# badge.net
KiCad netlist of a schematic drawn in Altium Designer
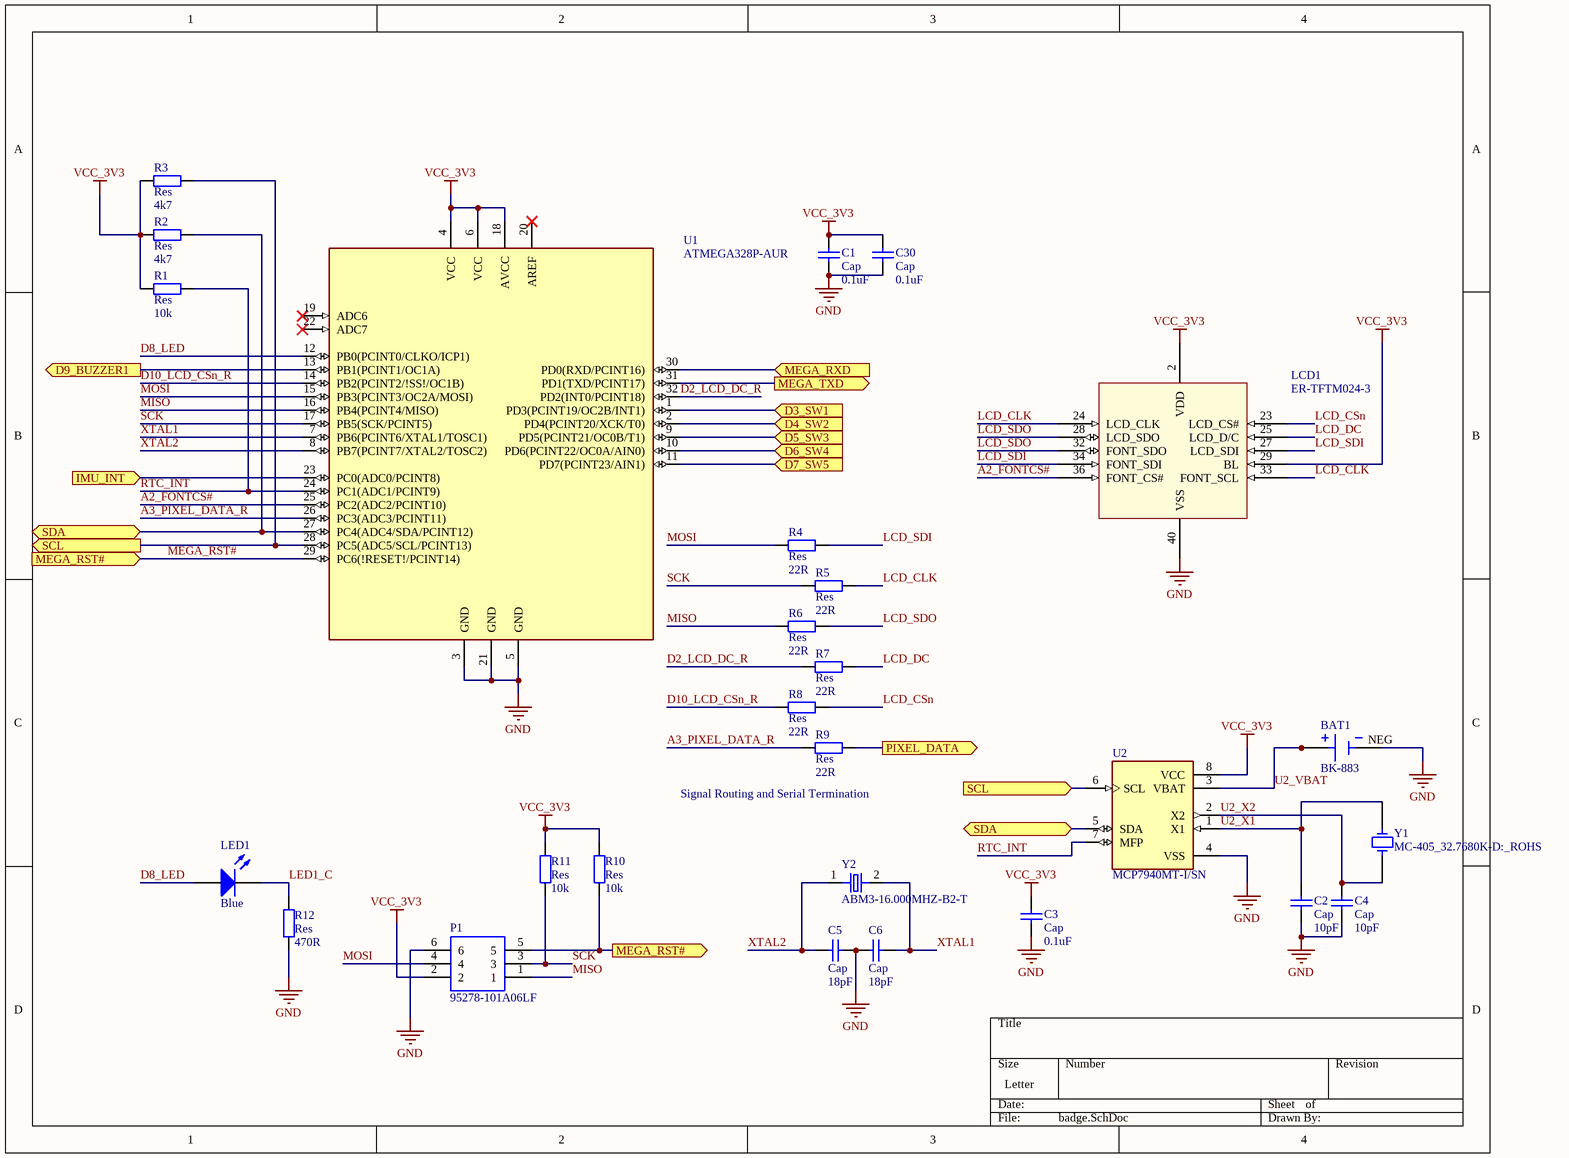
[diagram p0: badge.SchDoc]

(export (version "E")
  (design (tool "Eeschema 10.0.6"))
  (components
    (comp (ref "BAT1")
      (value "BK-883")
      (footprint "BAT_BK-883")
      (description "Battery Retainer Coin, 20.0mm 1 Cell SMD _SMT_ Tab")
      (fields (field (name "MF") "MPD _Memory") (field (name "MP") "BK-883-TR"))
      (libsource (lib "badge") (part "BK-883"))
    )
    (comp (ref "C1")
      (value "Cap")
      (footprint "C0603")
      (description "Capacitor")
      (fields
        (field (name "ALTIUM_VALUE") "0.1uF")
        (field (name "MP") "C0603C104Z3VACTU")
        (field (name "MF") "KEMET")
        (field (name "PUBLISHER") "Altium Limited")
      )
      (libsource (lib "badge") (part "Cap"))
    )
    (comp (ref "C2")
      (value "Cap")
      (footprint "C0603")
      (description "Capacitor")
      (fields
        (field (name "ALTIUM_VALUE") "10pF")
        (field (name "MF") "KEMET")
        (field (name "MP") "C0603C100J1GACTU")
        (field (name "PUBLISHER") "Altium Limited")
      )
      (libsource (lib "badge") (part "Cap"))
    )
    (comp (ref "C3")
      (value "Cap")
      (footprint "C0603")
      (description "Capacitor")
      (fields
        (field (name "ALTIUM_VALUE") "0.1uF")
        (field (name "MF") "KEMET")
        (field (name "MP") "C0603C104M4RACTU")
        (field (name "PUBLISHER") "Altium Limited")
      )
      (libsource (lib "badge") (part "Cap"))
    )
    (comp (ref "C4")
      (value "Cap")
      (footprint "C0603")
      (description "Capacitor")
      (fields
        (field (name "ALTIUM_VALUE") "10pF")
        (field (name "MF") "KEMET")
        (field (name "MP") "C0603C100J1GACTU")
        (field (name "PUBLISHER") "Altium Limited")
      )
      (libsource (lib "badge") (part "Cap"))
    )
    (comp (ref "C5")
      (value "Cap")
      (footprint "C0603")
      (description "Capacitor")
      (fields
        (field (name "ALTIUM_VALUE") "18pF")
        (field (name "MF") "KEMET")
        (field (name "MP") "C0603C180J5GACTU")
        (field (name "PUBLISHER") "Altium Limited")
      )
      (libsource (lib "badge") (part "Cap"))
    )
    (comp (ref "C6")
      (value "Cap")
      (footprint "C0603")
      (description "Capacitor")
      (fields
        (field (name "ALTIUM_VALUE") "18pF")
        (field (name "MF") "KEMET")
        (field (name "MP") "C0603C180J5GACTU")
        (field (name "PUBLISHER") "Altium Limited")
      )
      (libsource (lib "badge") (part "Cap"))
    )
    (comp (ref "C30")
      (value "Cap")
      (footprint "C0603")
      (description "Capacitor")
      (fields
        (field (name "ALTIUM_VALUE") "0.1uF")
        (field (name "MF") "KEMET")
        (field (name "MP") "C0603C104Z3VACTU")
        (field (name "PUBLISHER") "Altium Limited")
      )
      (libsource (lib "badge") (part "Cap"))
    )
    (comp (ref "LCD1")
      (value "ER-TFTM024-3")
      (footprint "ER-TFTM024-3")
      (fields (field (name "MF") "DNP"))
      (libsource (lib "badge") (part "ER-TFTM024-3"))
    )
    (comp (ref "LED1")
      (value "Blue")
      (footprint "L0603")
      (description "Typical INFRARED GaAs LED")
      (fields
        (field (name "MF") "OSRAM")
        (field (name "MP") "LB Q39G-L2OO-35-1")
        (field (name "PUBLISHER") "Altium Limited")
      )
      (libsource (lib "badge") (part "LED"))
    )
    (comp (ref "P1")
      (value "95278-101A06LF")
      (footprint "AMPHENOL_95278-101A06LF")
      (description "Connector Header Surface Mount 6 position 0.100 _2.54mm_")
      (fields (field (name "MF") "Amphenol ICC"))
      (libsource (lib "badge") (part "95278-101A06LF"))
    )
    (comp (ref "R1")
      (value "Res")
      (footprint "R0603")
      (description "Resistor")
      (fields
        (field (name "ALTIUM_VALUE") "10k")
        (field (name "MP") "RC0603JR-0710KL")
        (field (name "MF") "Yageo")
        (field (name "PUBLISHER") "Altium Limited")
      )
      (libsource (lib "badge") (part "Res"))
    )
    (comp (ref "R2")
      (value "Res")
      (footprint "R0603")
      (description "Resistor")
      (fields
        (field (name "ALTIUM_VALUE") "4k7")
        (field (name "MF") "Yageo")
        (field (name "MP") "RC0603JR-074K7L")
        (field (name "PUBLISHER") "Altium Limited")
      )
      (libsource (lib "badge") (part "Res"))
    )
    (comp (ref "R3")
      (value "Res")
      (footprint "R0603")
      (description "Resistor")
      (fields
        (field (name "ALTIUM_VALUE") "4k7")
        (field (name "MF") "Yageo")
        (field (name "MP") "RC0603JR-074K7L")
        (field (name "PUBLISHER") "Altium Limited")
      )
      (libsource (lib "badge") (part "Res"))
    )
    (comp (ref "R4")
      (value "Res")
      (footprint "R0603")
      (description "Resistor")
      (fields
        (field (name "ALTIUM_VALUE") "22R")
        (field (name "MF") "TE Connectivity")
        (field (name "MP") "CRGCQ0603J22R")
        (field (name "PUBLISHER") "Altium Limited")
      )
      (libsource (lib "badge") (part "Res"))
    )
    (comp (ref "R5")
      (value "Res")
      (footprint "R0603")
      (description "Resistor")
      (fields
        (field (name "ALTIUM_VALUE") "22R")
        (field (name "MF") "TE Connectivity")
        (field (name "MP") "CRGCQ0603J22R")
        (field (name "PUBLISHER") "Altium Limited")
      )
      (libsource (lib "badge") (part "Res"))
    )
    (comp (ref "R6")
      (value "Res")
      (footprint "R0603")
      (description "Resistor")
      (fields
        (field (name "ALTIUM_VALUE") "22R")
        (field (name "MF") "TE Connectivity")
        (field (name "MP") "CRGCQ0603J22R")
        (field (name "PUBLISHER") "Altium Limited")
      )
      (libsource (lib "badge") (part "Res"))
    )
    (comp (ref "R7")
      (value "Res")
      (footprint "R0603")
      (description "Resistor")
      (fields
        (field (name "ALTIUM_VALUE") "22R")
        (field (name "MF") "TE Connectivity")
        (field (name "MP") "CRGCQ0603J22R")
        (field (name "PUBLISHER") "Altium Limited")
      )
      (libsource (lib "badge") (part "Res"))
    )
    (comp (ref "R8")
      (value "Res")
      (footprint "R0603")
      (description "Resistor")
      (fields
        (field (name "ALTIUM_VALUE") "22R")
        (field (name "MF") "TE Connectivity")
        (field (name "MP") "CRGCQ0603J22R")
        (field (name "PUBLISHER") "Altium Limited")
      )
      (libsource (lib "badge") (part "Res"))
    )
    (comp (ref "R9")
      (value "Res")
      (footprint "R0603")
      (description "Resistor")
      (fields
        (field (name "ALTIUM_VALUE") "22R")
        (field (name "MF") "TE Connectivity")
        (field (name "MP") "CRGCQ0603J22R")
        (field (name "PUBLISHER") "Altium Limited")
      )
      (libsource (lib "badge") (part "Res"))
    )
    (comp (ref "R10")
      (value "Res")
      (footprint "R0603")
      (description "Resistor")
      (fields
        (field (name "ALTIUM_VALUE") "10k")
        (field (name "MP") "RC0603JR-0710KL")
        (field (name "MF") "Yageo")
        (field (name "PUBLISHER") "Altium Limited")
      )
      (libsource (lib "") (part "Res_1"))
    )
    (comp (ref "R11")
      (value "Res")
      (footprint "R0603")
      (description "Resistor")
      (fields
        (field (name "ALTIUM_VALUE") "10k")
        (field (name "MP") "RC0603JR-0710KL")
        (field (name "MF") "Yageo")
        (field (name "PUBLISHER") "Altium Limited")
      )
      (libsource (lib "") (part "Res_1"))
    )
    (comp (ref "R12")
      (value "Res")
      (footprint "R0603")
      (description "Resistor")
      (fields
        (field (name "ALTIUM_VALUE") "470R")
        (field (name "MF") "TE Connectivity")
        (field (name "MP") "CRGCQ0603J470R")
        (field (name "PUBLISHER") "Altium Limited")
      )
      (libsource (lib "") (part "Res_1"))
    )
    (comp (ref "U1")
      (value "ATMEGA328P-AUR")
      (footprint "QFP80P900X900X120-32N")
      (description "AVR AVRÂ® ATmega Microcontroller IC 8-Bit 20MHz 32KB _16K x 16_ FLASH 32-TQFP _7x7_")
      (fields (field (name "MF") "Microchip") (field (name "DIGI-KEY_PART_NUMBER") "ATMEGA328P-AURCT-ND"))
      (libsource (lib "badge") (part "ATMEGA328P-AUR"))
    )
    (comp (ref "U2")
      (value "MCP7940MT-I/SN")
      (footprint "SOIC127P600X175-8N")
      (description "Real Time Clock _RTC_ IC Clock/Calendar 64B IÂ²C, 2-Wire Serial 8-SOIC _0.154, 3.90mm Width_")
      (fields (field (name "MF") "Microchip"))
      (libsource (lib "badge") (part "MCP7940MT-I/SN"))
    )
    (comp (ref "Y1")
      (value "MC-405_32.7680K-D:_ROHS")
      (footprint "XTAL320X150")
      (description "32.768kHz Â±20ppm Crystal 35 kOhms 4-SOJ, 2.29mm pitch")
      (fields (field (name "MP") "DNP"))
      (libsource (lib "badge") (part "MC-405_32.7680K-D{colon}_ROHS"))
    )
    (comp (ref "Y2")
      (value "ABM3-16.000MHZ-B2-T")
      (footprint "XTAL_ECS-100-20-5PVX")
      (description "16MHz Â±20ppm Crystal 18pF 40 Ohms 2-SMD, No Lead")
      (fields (field (name "MP") "DNP") (field (name "DIGI-KEY_PART_NUMBER") "535-9103-1-ND"))
      (libsource (lib "badge") (part "ABM3-16.000MHZ-B2-T"))
    )
  )
  (nets
    (net (code "1") (name "/A2_FONTCS#") (class "Default")
      (node (ref "LCD1") (pin "36") (pinfunction "FONT_CS#_36") (pintype "input"))
      (node (ref "U1") (pin "25") (pinfunction "PC2(ADC2/PCINT10)_25") (pintype "bidirectional"))
    )
    (net (code "2") (name "/A3_PIXEL_DATA_R") (class "Default")
      (node (ref "R9") (pin "1") (pinfunction "1_1") (pintype "passive"))
      (node (ref "U1") (pin "26") (pinfunction "PC3(ADC3/PCINT11)_26") (pintype "bidirectional"))
    )
    (net (code "3") (name "/D2_LCD_DC_R") (class "Default")
      (node (ref "R7") (pin "1") (pinfunction "1_1") (pintype "passive"))
      (node (ref "U1") (pin "32") (pinfunction "PD2(INT0/PCINT18)_32") (pintype "bidirectional"))
    )
    (net (code "4") (name "/D3_SW1") (class "Default")
      (node (ref "U1") (pin "1") (pinfunction "PD3(PCINT19/OC2B/INT1)_1") (pintype "bidirectional"))
    )
    (net (code "5") (name "/D4_SW2") (class "Default")
      (node (ref "U1") (pin "2") (pinfunction "PD4(PCINT20/XCK/T0)_2") (pintype "bidirectional"))
    )
    (net (code "6") (name "/D5_SW3") (class "Default")
      (node (ref "U1") (pin "9") (pinfunction "PD5(PCINT21/OC0B/T1)_9") (pintype "bidirectional"))
    )
    (net (code "7") (name "/D6_SW4") (class "Default")
      (node (ref "U1") (pin "10") (pinfunction "PD6(PCINT22/OC0A/AIN0)_10") (pintype "bidirectional"))
    )
    (net (code "8") (name "/D7_SW5") (class "Default")
      (node (ref "U1") (pin "11") (pinfunction "PD7(PCINT23/AIN1)_11") (pintype "bidirectional"))
    )
    (net (code "9") (name "/D8_LED") (class "Default")
      (node (ref "LED1") (pin "1") (pinfunction "A_1") (pintype "passive"))
      (node (ref "U1") (pin "12") (pinfunction "PB0(PCINT0/CLKO/ICP1)_12") (pintype "bidirectional"))
    )
    (net (code "10") (name "/D9_BUZZER1") (class "Default")
      (node (ref "U1") (pin "13") (pinfunction "PB1(PCINT1/OC1A)_13") (pintype "bidirectional"))
    )
    (net (code "11") (name "/D10_LCD_CSn_R") (class "Default")
      (node (ref "R8") (pin "1") (pinfunction "1_1") (pintype "passive"))
      (node (ref "U1") (pin "14") (pinfunction "PB2(PCINT2/!SS!/OC1B)_14") (pintype "bidirectional"))
    )
    (net (code "12") (name "/IMU_INT") (class "Default")
      (node (ref "U1") (pin "23") (pinfunction "PC0(ADC0/PCINT8)_23") (pintype "bidirectional"))
    )
    (net (code "13") (name "/LCD_CLK") (class "Default")
      (node (ref "LCD1") (pin "24") (pinfunction "LCD_CLK_24") (pintype "input"))
      (node (ref "LCD1") (pin "33") (pinfunction "FONT_SCL_33") (pintype "input"))
      (node (ref "R5") (pin "2") (pinfunction "2_2") (pintype "passive"))
    )
    (net (code "14") (name "/LCD_CSn") (class "Default")
      (node (ref "LCD1") (pin "23") (pinfunction "LCD_CS#_23") (pintype "input"))
      (node (ref "R8") (pin "2") (pinfunction "2_2") (pintype "passive"))
    )
    (net (code "15") (name "/LCD_DC") (class "Default")
      (node (ref "LCD1") (pin "25") (pinfunction "LCD_D/C_25") (pintype "input"))
      (node (ref "R7") (pin "2") (pinfunction "2_2") (pintype "passive"))
    )
    (net (code "16") (name "/LCD_SDI") (class "Default")
      (node (ref "LCD1") (pin "27") (pinfunction "LCD_SDI_27") (pintype "input"))
      (node (ref "LCD1") (pin "34") (pinfunction "FONT_SDI_34") (pintype "input"))
      (node (ref "R4") (pin "2") (pinfunction "2_2") (pintype "passive"))
    )
    (net (code "17") (name "/LCD_SDO") (class "Default")
      (node (ref "LCD1") (pin "28") (pinfunction "LCD_SDO_28") (pintype "bidirectional"))
      (node (ref "LCD1") (pin "32") (pinfunction "FONT_SDO_32") (pintype "bidirectional"))
      (node (ref "R6") (pin "2") (pinfunction "2_2") (pintype "passive"))
    )
    (net (code "18") (name "/LED1_C") (class "Default")
      (node (ref "LED1") (pin "2") (pinfunction "K_2") (pintype "passive"))
      (node (ref "R12") (pin "2") (pinfunction "2_2") (pintype "passive"))
    )
    (net (code "19") (name "/MEGA_RST#") (class "Default")
      (node (ref "P1") (pin "5") (pinfunction "5_5") (pintype "passive"))
      (node (ref "R10") (pin "1") (pinfunction "1_1") (pintype "passive"))
      (node (ref "U1") (pin "29") (pinfunction "PC6(!RESET!/PCINT14)_29") (pintype "bidirectional"))
    )
    (net (code "20") (name "/MEGA_RXD") (class "Default")
      (node (ref "U1") (pin "30") (pinfunction "PD0(RXD/PCINT16)_30") (pintype "bidirectional"))
    )
    (net (code "21") (name "/MEGA_TXD") (class "Default")
      (node (ref "U1") (pin "31") (pinfunction "PD1(TXD/PCINT17)_31") (pintype "bidirectional"))
    )
    (net (code "22") (name "/MISO") (class "Default")
      (node (ref "P1") (pin "1") (pinfunction "1_1") (pintype "passive"))
      (node (ref "R6") (pin "1") (pinfunction "1_1") (pintype "passive"))
      (node (ref "U1") (pin "16") (pinfunction "PB4(PCINT4/MISO)_16") (pintype "bidirectional"))
    )
    (net (code "23") (name "/MOSI") (class "Default")
      (node (ref "P1") (pin "4") (pinfunction "4_4") (pintype "passive"))
      (node (ref "R4") (pin "1") (pinfunction "1_1") (pintype "passive"))
      (node (ref "U1") (pin "15") (pinfunction "PB3(PCINT3/OC2A/MOSI)_15") (pintype "bidirectional"))
    )
    (net (code "24") (name "/PIXEL_DATA") (class "Default")
      (node (ref "R9") (pin "2") (pinfunction "2_2") (pintype "passive"))
    )
    (net (code "25") (name "/RTC_INT") (class "Default")
      (node (ref "R1") (pin "2") (pinfunction "2_2") (pintype "passive"))
      (node (ref "U1") (pin "24") (pinfunction "PC1(ADC1/PCINT9)_24") (pintype "bidirectional"))
      (node (ref "U2") (pin "7") (pinfunction "MFP_7") (pintype "bidirectional"))
    )
    (net (code "26") (name "/SCK") (class "Default")
      (node (ref "P1") (pin "3") (pinfunction "3_3") (pintype "passive"))
      (node (ref "R11") (pin "1") (pinfunction "1_1") (pintype "passive"))
      (node (ref "R5") (pin "1") (pinfunction "1_1") (pintype "passive"))
      (node (ref "U1") (pin "17") (pinfunction "PB5(SCK/PCINT5)_17") (pintype "bidirectional"))
    )
    (net (code "27") (name "/SCL") (class "Default")
      (node (ref "R3") (pin "2") (pinfunction "2_2") (pintype "passive"))
      (node (ref "U1") (pin "28") (pinfunction "PC5(ADC5/SCL/PCINT13)_28") (pintype "bidirectional"))
      (node (ref "U2") (pin "6") (pinfunction "SCL_6") (pintype "input"))
    )
    (net (code "28") (name "/SDA") (class "Default")
      (node (ref "R2") (pin "2") (pinfunction "2_2") (pintype "passive"))
      (node (ref "U1") (pin "27") (pinfunction "PC4(ADC4/SDA/PCINT12)_27") (pintype "bidirectional"))
      (node (ref "U2") (pin "5") (pinfunction "SDA_5") (pintype "bidirectional"))
    )
    (net (code "29") (name "/U2_VBAT") (class "Default")
      (node (ref "BAT1") (pin "S1+") (pinfunction "POS_S1+") (pintype "passive"))
      (node (ref "BAT1") (pin "S2+") (pinfunction "POS_S2+") (pintype "passive"))
      (node (ref "U2") (pin "3") (pinfunction "VBAT_3") (pintype "power_in"))
    )
    (net (code "30") (name "/U2_X1") (class "Default")
      (node (ref "C2") (pin "2") (pinfunction "2_2") (pintype "passive"))
      (node (ref "U2") (pin "1") (pinfunction "X1_1") (pintype "input"))
      (node (ref "Y1") (pin "2") (pinfunction "2_2") (pintype "passive"))
    )
    (net (code "31") (name "/U2_X2") (class "Default")
      (node (ref "C4") (pin "2") (pinfunction "2_2") (pintype "passive"))
      (node (ref "U2") (pin "2") (pinfunction "X2_2") (pintype "output"))
      (node (ref "Y1") (pin "1") (pinfunction "1_1") (pintype "passive"))
    )
    (net (code "32") (name "/XTAL1") (class "Default")
      (node (ref "C6") (pin "2") (pinfunction "2_2") (pintype "passive"))
      (node (ref "U1") (pin "7") (pinfunction "PB6(PCINT6/XTAL1/TOSC1)_7") (pintype "bidirectional"))
      (node (ref "Y2") (pin "2") (pinfunction "2_2") (pintype "passive"))
    )
    (net (code "33") (name "/XTAL2") (class "Default")
      (node (ref "C5") (pin "1") (pinfunction "1_1") (pintype "passive"))
      (node (ref "U1") (pin "8") (pinfunction "PB7(PCINT7/XTAL2/TOSC2)_8") (pintype "bidirectional"))
      (node (ref "Y2") (pin "1") (pinfunction "1_1") (pintype "passive"))
    )
    (net (code "34") (name "GND") (class "Default")
      (node (ref "BAT1") (pin "NEG") (pinfunction "NEG_NEG") (pintype "passive"))
      (node (ref "C1") (pin "1") (pinfunction "1_1") (pintype "passive"))
      (node (ref "C2") (pin "1") (pinfunction "1_1") (pintype "passive"))
      (node (ref "C3") (pin "1") (pinfunction "1_1") (pintype "passive"))
      (node (ref "C30") (pin "1") (pinfunction "1_1") (pintype "passive"))
      (node (ref "C4") (pin "1") (pinfunction "1_1") (pintype "passive"))
      (node (ref "C5") (pin "2") (pinfunction "2_2") (pintype "passive"))
      (node (ref "C6") (pin "1") (pinfunction "1_1") (pintype "passive"))
      (node (ref "LCD1") (pin "40") (pinfunction "VSS_40") (pintype "passive"))
      (node (ref "P1") (pin "6") (pinfunction "6_6") (pintype "passive"))
      (node (ref "R12") (pin "1") (pinfunction "1_1") (pintype "passive"))
      (node (ref "U1") (pin "21") (pinfunction "GND_21") (pintype "power_in"))
      (node (ref "U1") (pin "3") (pinfunction "GND_3") (pintype "power_in"))
      (node (ref "U1") (pin "5") (pinfunction "GND_5") (pintype "power_in"))
      (node (ref "U2") (pin "4") (pinfunction "VSS_4") (pintype "passive"))
    )
    (net (code "35") (name "VCC_3V3") (class "Default")
      (node (ref "C1") (pin "2") (pinfunction "2_2") (pintype "passive"))
      (node (ref "C3") (pin "2") (pinfunction "2_2") (pintype "passive"))
      (node (ref "C30") (pin "2") (pinfunction "2_2") (pintype "passive"))
      (node (ref "LCD1") (pin "2") (pinfunction "VDD_2") (pintype "power_in"))
      (node (ref "LCD1") (pin "29") (pinfunction "BL_29") (pintype "input"))
      (node (ref "P1") (pin "2") (pinfunction "2_2") (pintype "passive"))
      (node (ref "R1") (pin "1") (pinfunction "1_1") (pintype "passive"))
      (node (ref "R10") (pin "2") (pinfunction "2_2") (pintype "passive"))
      (node (ref "R11") (pin "2") (pinfunction "2_2") (pintype "passive"))
      (node (ref "R2") (pin "1") (pinfunction "1_1") (pintype "passive"))
      (node (ref "R3") (pin "1") (pinfunction "1_1") (pintype "passive"))
      (node (ref "U1") (pin "18") (pinfunction "AVCC_18") (pintype "power_in"))
      (node (ref "U1") (pin "4") (pinfunction "VCC_4") (pintype "power_in"))
      (node (ref "U1") (pin "6") (pinfunction "VCC_6") (pintype "power_in"))
      (node (ref "U2") (pin "8") (pinfunction "VCC_8") (pintype "power_in"))
    )
    (net (code "36") (name "unconnected-(U1-ADC6-Pad19)") (class "Default")
      (node (ref "U1") (pin "19") (pinfunction "ADC6_19") (pintype "input+no_connect"))
    )
    (net (code "37") (name "unconnected-(U1-ADC7-Pad22)") (class "Default")
      (node (ref "U1") (pin "22") (pinfunction "ADC7_22") (pintype "input+no_connect"))
    )
    (net (code "38") (name "unconnected-(U1-AREF-Pad20)") (class "Default")
      (node (ref "U1") (pin "20") (pinfunction "AREF_20") (pintype "power_in+no_connect"))
    )
  )
)
